# 06_-_CPU_-_ETHERNET_SATA.net
KiCad netlist of a schematic drawn in Altium Designer
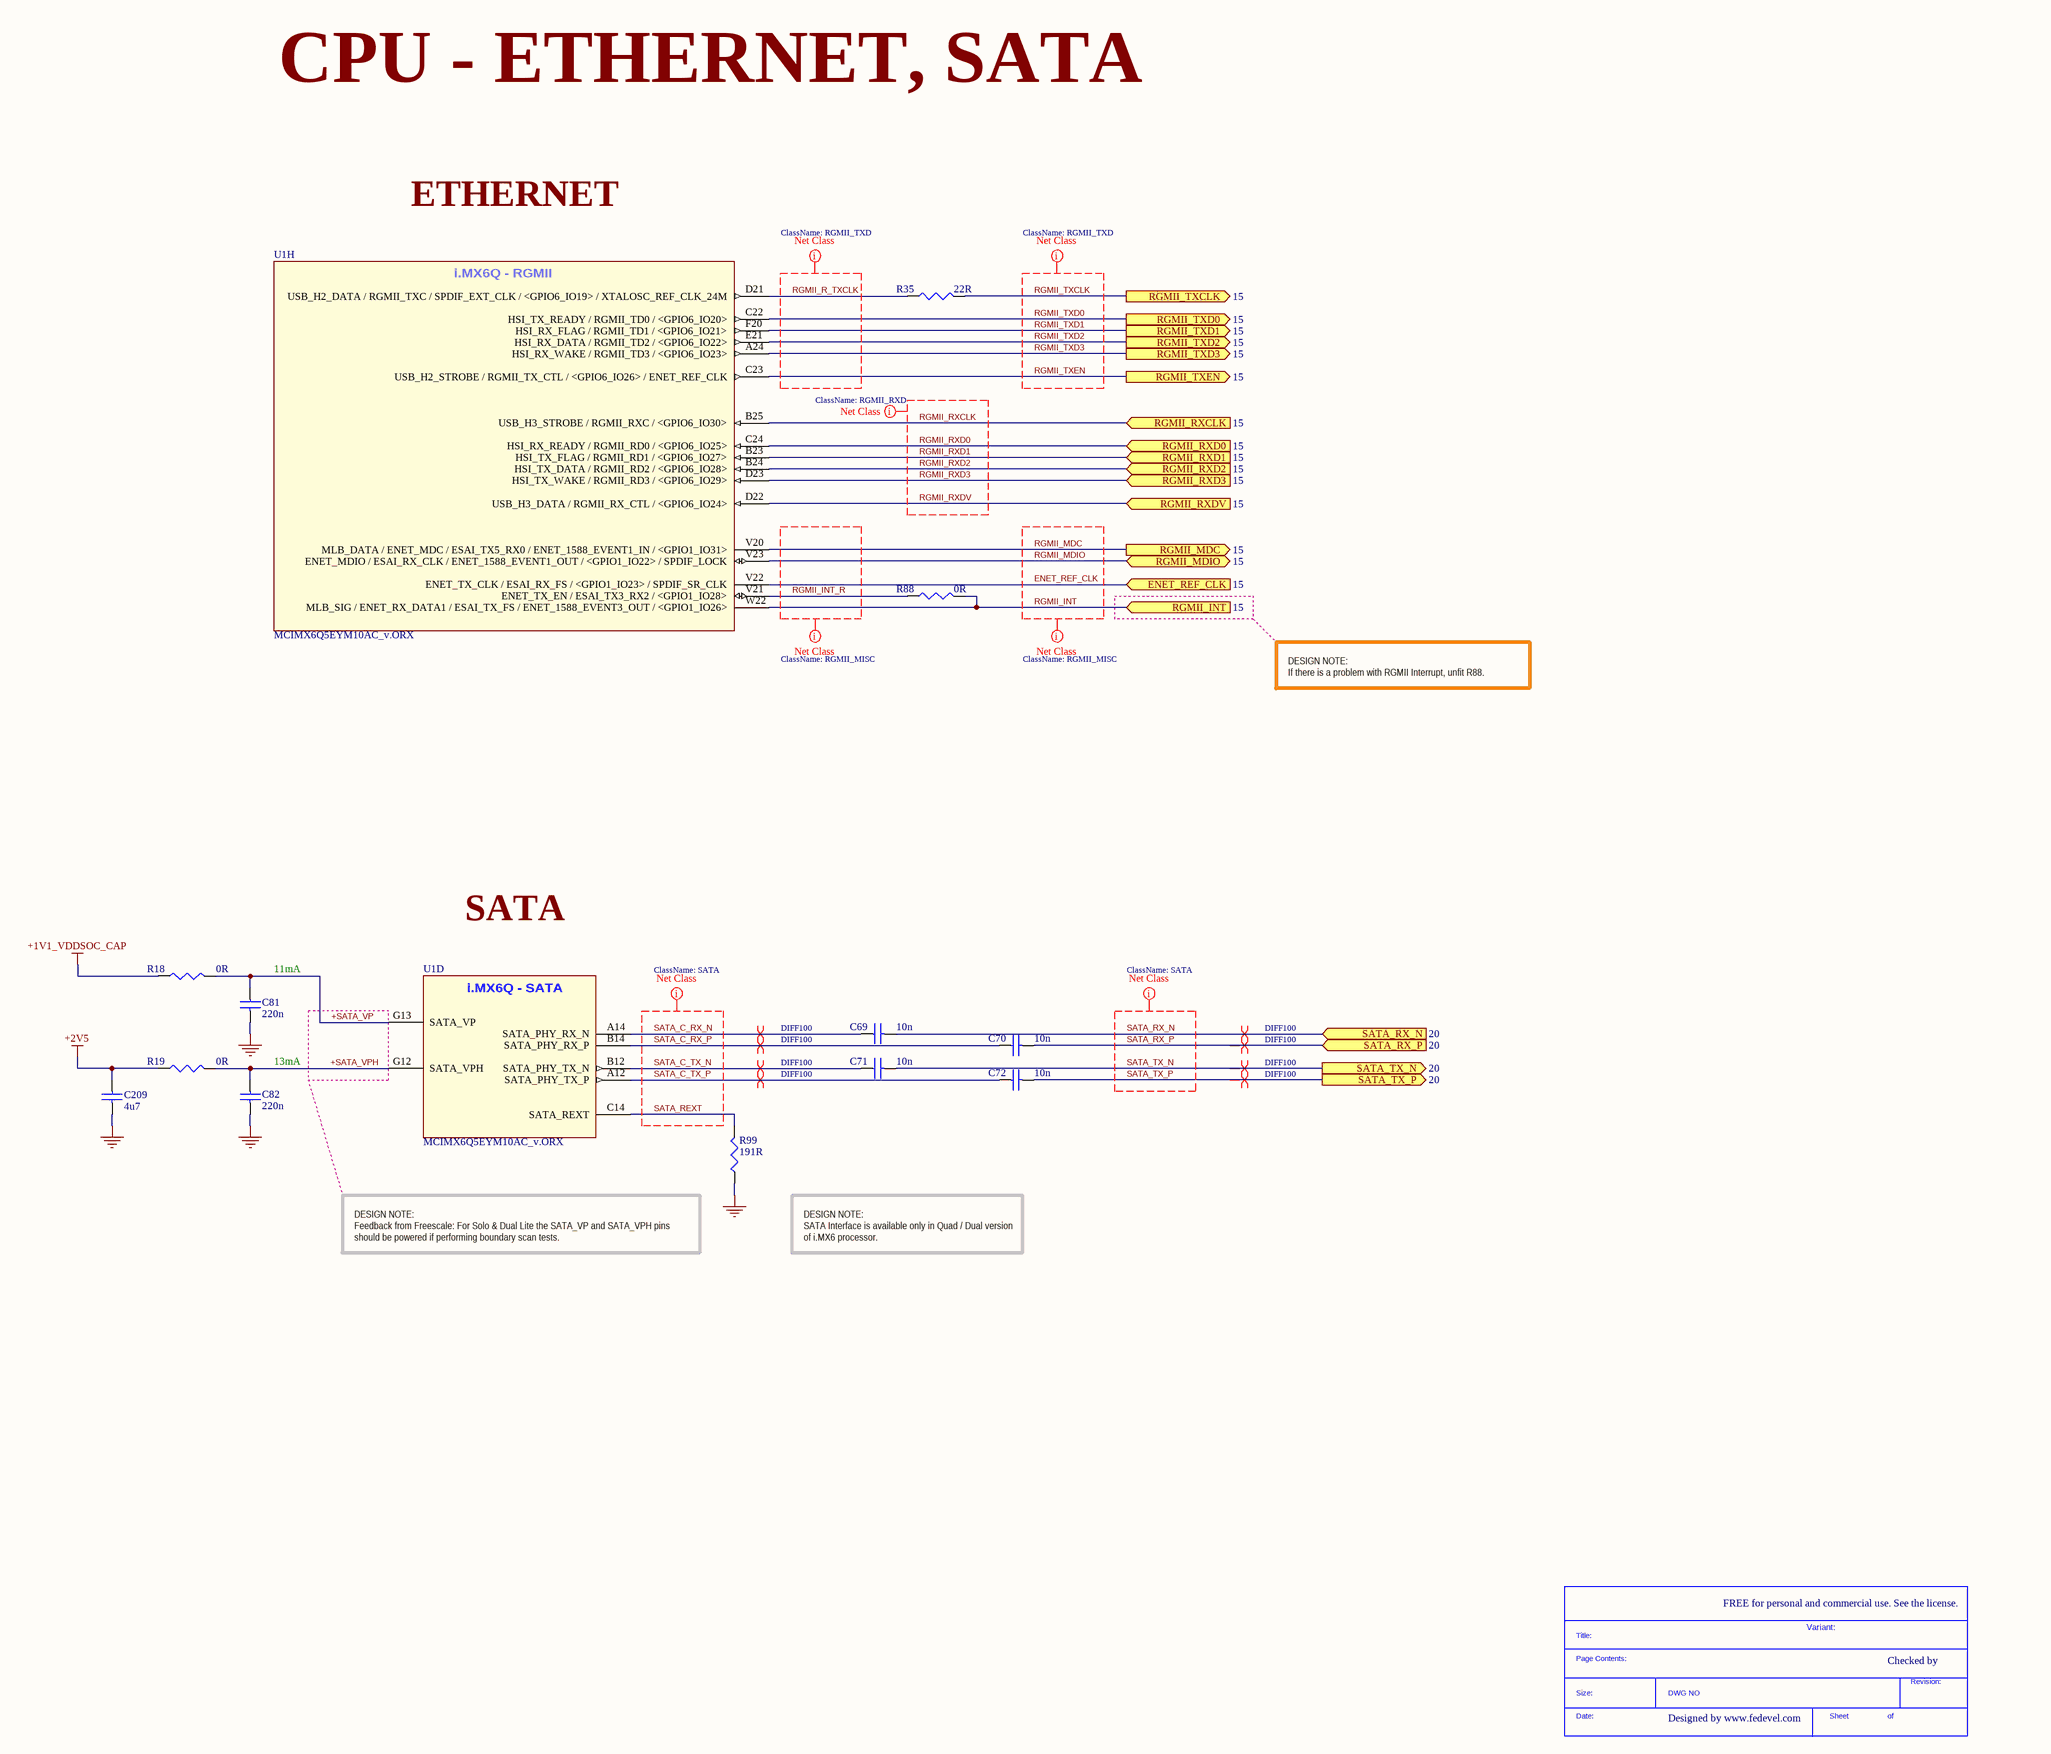
[diagram p0: [06] - CPU - ETHERNET, SATA.SchDoc]

(export (version "E")
  (design (tool "Eeschema 10.0.6"))
  (components
    (comp (ref "C69")
      (value "10n")
      (footprint "C0402")
      (description "CAP CER 10000PF 50V 10% X7R 0402")
      (fields
        (field (name "MANUFACTURER") "TDK Corporation")
        (field (name "MANUFACTURER PART NUMBER") "C1005X7R1H103K")
      )
      (libsource (lib "Integrated_Library_FEDEVEL_APR_2015") (part "C1005X7R1H103K"))
    )
    (comp (ref "C70")
      (value "10n")
      (footprint "C0402")
      (description "CAP CER 10000PF 50V 10% X7R 0402")
      (fields
        (field (name "MANUFACTURER") "TDK Corporation")
        (field (name "MANUFACTURER PART NUMBER") "C1005X7R1H103K")
      )
      (libsource (lib "Integrated_Library_FEDEVEL_APR_2015") (part "C1005X7R1H103K"))
    )
    (comp (ref "C71")
      (value "10n")
      (footprint "C0402")
      (description "CAP CER 10000PF 50V 10% X7R 0402")
      (fields
        (field (name "MANUFACTURER") "TDK Corporation")
        (field (name "MANUFACTURER PART NUMBER") "C1005X7R1H103K")
      )
      (libsource (lib "Integrated_Library_FEDEVEL_APR_2015") (part "C1005X7R1H103K"))
    )
    (comp (ref "C72")
      (value "10n")
      (footprint "C0402")
      (description "CAP CER 10000PF 50V 10% X7R 0402")
      (fields
        (field (name "MANUFACTURER") "TDK Corporation")
        (field (name "MANUFACTURER PART NUMBER") "C1005X7R1H103K")
      )
      (libsource (lib "Integrated_Library_FEDEVEL_APR_2015") (part "C1005X7R1H103K"))
    )
    (comp (ref "C81")
      (value "220n")
      (footprint "C0201")
      (description "CAP CER 0.22UF 6.3V 20% X5R 0201")
      (fields
        (field (name "MANUFACTURER") "TDK Corporation")
        (field (name "MANUFACTURER PART NUMBER") "C0603X5R0J224M030BB")
        (field (name ".CHECKED PCB") "MM")
        (field (name ".CHECKED SCH") "MM")
        (field (name ".CREATOR") "MM")
      )
      (libsource (lib "Integrated_Library_FEDEVEL_0201") (part "C0603X5R0J224M030BB"))
    )
    (comp (ref "C82")
      (value "220n")
      (footprint "C0201")
      (description "CAP CER 0.22UF 6.3V 20% X5R 0201")
      (fields
        (field (name "MANUFACTURER") "TDK Corporation")
        (field (name "MANUFACTURER PART NUMBER") "C0603X5R0J224M030BB")
        (field (name ".CHECKED PCB") "MM")
        (field (name ".CHECKED SCH") "MM")
        (field (name ".CREATOR") "MM")
      )
      (libsource (lib "Integrated_Library_FEDEVEL_0201") (part "C0603X5R0J224M030BB"))
    )
    (comp (ref "C209")
      (value "4u7")
      (footprint "C0402")
      (description "CAP CER 4.7UF 10V 20% X5R 0402")
      (fields
        (field (name "MANUFACTURER") "TDK Corporation")
        (field (name "MANUFACTURER PART NUMBER") "C1005X5R1A475M")
      )
      (libsource (lib "Integrated_Library_FEDEVEL_APR_2015") (part "C1005X5R1A475M"))
    )
    (comp (ref "R18")
      (value "0R")
      (footprint "R0402")
      (description "RES 0.0 OHM 1/16W 0402 SMD")
      (fields
        (field (name "MANUFACTURER") "Yageo")
        (field (name "MANUFACTURER PART NUMBER") "RC0402JR-070RL")
      )
      (libsource (lib "Integrated_Library_FEDEVEL_APR_2015") (part "RC0402JR-070RL"))
    )
    (comp (ref "R19")
      (value "0R")
      (footprint "R0402")
      (description "RES 0.0 OHM 1/16W 0402 SMD")
      (fields
        (field (name "MANUFACTURER") "Yageo")
        (field (name "MANUFACTURER PART NUMBER") "RC0402JR-070RL")
      )
      (libsource (lib "Integrated_Library_FEDEVEL_APR_2015") (part "RC0402JR-070RL"))
    )
    (comp (ref "R35")
      (value "22R")
      (footprint "R0402")
      (description "RES 22.0 OHM 1/16W 1% 0402 SMD")
      (fields
        (field (name "MANUFACTURER") "Yageo")
        (field (name "MANUFACTURER PART NUMBER") "RC0402FR-0722RL")
      )
      (libsource (lib "Integrated_Library_FEDEVEL_APR_2015") (part "RC0402FR-0722RL"))
    )
    (comp (ref "R88")
      (value "0R")
      (footprint "R0402")
      (description "RES 0.0 OHM 1/16W 0402 SMD")
      (fields
        (field (name "MANUFACTURER") "Yageo")
        (field (name "MANUFACTURER PART NUMBER") "RC0402JR-070RL")
      )
      (libsource (lib "Integrated_Library_FEDEVEL_APR_2015") (part "RC0402JR-070RL"))
    )
    (comp (ref "R99")
      (value "191R")
      (footprint "R0201")
      (description "RES 191 OHM 1/20W 1% 0201 SMD")
      (fields
        (field (name "MANUFACTURER") "Panasonic Electronic Components")
        (field (name "MANUFACTURER PART NUMBER") "ERJ-1GEF1910C")
        (field (name ".CREATOR") "MM")
        (field (name ".CHECKED PCB") "MM")
        (field (name ".CHECKED SCH") "MM")
      )
      (libsource (lib "Integrated_Library_FEDEVEL_0201") (part "ERJ-1GEF1910C"))
    )
    (comp (ref "U1")
      (value "MCIMX6Q5EYM10AC_v.ORX")
      (footprint "PBGA624")
      (description "IC MCU 32BIT ARM QUAD 624FCBGA")
      (fields
        (field (name "MANUFACTURER") "Freescale Semiconductor")
        (field (name "MANUFACTURER PART NUMBER") "MCIMX6Q5EYM10AC")
        (field (name ".CREATOR") "MM")
        (field (name ".CHECKED PCB") "MM, checked by RF")
      )
      (libsource (lib "Integrated_Library_FEDEVEL_APR_2015") (part "MCIMX6Q5EYM10AC_v.ORX"))
    )
  )
  (nets
    (net (code "1") (name "+1V1_VDDSOC_CAP") (class "Default")
      (node (ref "R18") (pin "1") (pinfunction "1_1") (pintype "passive"))
    )
    (net (code "2") (name "+2V5") (class "Default")
      (node (ref "C209") (pin "1") (pinfunction "1_1") (pintype "passive"))
      (node (ref "R19") (pin "1") (pinfunction "1_1") (pintype "passive"))
    )
    (net (code "3") (name "/+SATA_VP") (class "Default")
      (node (ref "C81") (pin "1") (pinfunction "1_1") (pintype "passive"))
      (node (ref "R18") (pin "2") (pinfunction "2_2") (pintype "passive"))
      (node (ref "U1") (pin "G13") (pinfunction "SATA_VP_G13") (pintype "power_in"))
    )
    (net (code "4") (name "/+SATA_VPH") (class "Default")
      (node (ref "C82") (pin "1") (pinfunction "1_1") (pintype "passive"))
      (node (ref "R19") (pin "2") (pinfunction "2_2") (pintype "passive"))
      (node (ref "U1") (pin "G12") (pinfunction "SATA_VPH_G12") (pintype "power_in"))
    )
    (net (code "5") (name "/ENET_REF_CLK") (class "Default")
      (node (ref "U1") (pin "V22") (pinfunction "ENET_TX_CLK_/_ESAI_RX_FS_/_<GPIO1_IO23>_/_SPDIF_SR_CLK_V22") (pintype "passive"))
    )
    (net (code "6") (name "/RGMII_INT") (class "Default")
      (node (ref "R88") (pin "2") (pinfunction "2_2") (pintype "passive"))
      (node (ref "U1") (pin "W22") (pinfunction "MLB_SIG_/_ENET_RX_DATA1_/_ESAI_TX_FS_/_ENET_1588_EVENT3_OUT_/_<GPIO1_IO26>_W22") (pintype "passive"))
    )
    (net (code "7") (name "/RGMII_INT_R") (class "Default")
      (node (ref "R88") (pin "1") (pinfunction "1_1") (pintype "passive"))
      (node (ref "U1") (pin "V21") (pinfunction "ENET_TX_EN_/_ESAI_TX3_RX2_/_<GPIO1_IO28>_V21") (pintype "bidirectional"))
    )
    (net (code "8") (name "/RGMII_MDC") (class "Default")
      (node (ref "U1") (pin "V20") (pinfunction "MLB_DATA_/_ENET_MDC_/_ESAI_TX5_RX0_/_ENET_1588_EVENT1_IN_/_<GPIO1_IO31>_V20") (pintype "passive"))
    )
    (net (code "9") (name "/RGMII_MDIO") (class "Default")
      (node (ref "U1") (pin "V23") (pinfunction "ENET_MDIO_/_ESAI_RX_CLK_/_ENET_1588_EVENT1_OUT_/_<GPIO1_IO22>_/_SPDIF_LOCK_V23") (pintype "bidirectional"))
    )
    (net (code "10") (name "/RGMII_RXCLK") (class "Default")
      (node (ref "U1") (pin "B25") (pinfunction "USB_H3_STROBE_/_RGMII_RXC_/_<GPIO6_IO30>_B25") (pintype "input"))
    )
    (net (code "11") (name "/RGMII_RXD0") (class "Default")
      (node (ref "U1") (pin "C24") (pinfunction "HSI_RX_READY_/_RGMII_RD0_/_<GPIO6_IO25>_C24") (pintype "input"))
    )
    (net (code "12") (name "/RGMII_RXD1") (class "Default")
      (node (ref "U1") (pin "B23") (pinfunction "HSI_TX_FLAG_/_RGMII_RD1_/_<GPIO6_IO27>_B23") (pintype "input"))
    )
    (net (code "13") (name "/RGMII_RXD2") (class "Default")
      (node (ref "U1") (pin "B24") (pinfunction "HSI_TX_DATA_/_RGMII_RD2_/_<GPIO6_IO28>_B24") (pintype "input"))
    )
    (net (code "14") (name "/RGMII_RXD3") (class "Default")
      (node (ref "U1") (pin "D23") (pinfunction "HSI_TX_WAKE_/_RGMII_RD3_/_<GPIO6_IO29>_D23") (pintype "input"))
    )
    (net (code "15") (name "/RGMII_RXDV") (class "Default")
      (node (ref "U1") (pin "D22") (pinfunction "USB_H3_DATA_/_RGMII_RX_CTL_/_<GPIO6_IO24>_D22") (pintype "input"))
    )
    (net (code "16") (name "/RGMII_R_TXCLK") (class "Default")
      (node (ref "R35") (pin "1") (pinfunction "1_1") (pintype "passive"))
      (node (ref "U1") (pin "D21") (pinfunction "USB_H2_DATA_/_RGMII_TXC_/_SPDIF_EXT_CLK_/_<GPIO6_IO19>_/_XTALOSC_REF_CLK_24M_D21") (pintype "output"))
    )
    (net (code "17") (name "/RGMII_TXCLK") (class "Default")
      (node (ref "R35") (pin "2") (pinfunction "2_2") (pintype "passive"))
    )
    (net (code "18") (name "/RGMII_TXD0") (class "Default")
      (node (ref "U1") (pin "C22") (pinfunction "HSI_TX_READY_/_RGMII_TD0_/_<GPIO6_IO20>_C22") (pintype "output"))
    )
    (net (code "19") (name "/RGMII_TXD1") (class "Default")
      (node (ref "U1") (pin "F20") (pinfunction "HSI_RX_FLAG_/_RGMII_TD1_/_<GPIO6_IO21>_F20") (pintype "output"))
    )
    (net (code "20") (name "/RGMII_TXD2") (class "Default")
      (node (ref "U1") (pin "E21") (pinfunction "HSI_RX_DATA_/_RGMII_TD2_/_<GPIO6_IO22>_E21") (pintype "output"))
    )
    (net (code "21") (name "/RGMII_TXD3") (class "Default")
      (node (ref "U1") (pin "A24") (pinfunction "HSI_RX_WAKE_/_RGMII_TD3_/_<GPIO6_IO23>_A24") (pintype "output"))
    )
    (net (code "22") (name "/RGMII_TXEN") (class "Default")
      (node (ref "U1") (pin "C23") (pinfunction "USB_H2_STROBE_/_RGMII_TX_CTL_/_<GPIO6_IO26>_/_ENET_REF_CLK_C23") (pintype "output"))
    )
    (net (code "23") (name "/SATA_C_RX_N") (class "Default")
      (node (ref "C69") (pin "1") (pinfunction "1_1") (pintype "passive"))
      (node (ref "U1") (pin "A14") (pinfunction "SATA_PHY_RX_N_A14") (pintype "passive"))
    )
    (net (code "24") (name "/SATA_C_RX_P") (class "Default")
      (node (ref "C70") (pin "1") (pinfunction "1_1") (pintype "passive"))
      (node (ref "U1") (pin "B14") (pinfunction "SATA_PHY_RX_P_B14") (pintype "passive"))
    )
    (net (code "25") (name "/SATA_C_TX_N") (class "Default")
      (node (ref "C71") (pin "1") (pinfunction "1_1") (pintype "passive"))
      (node (ref "U1") (pin "B12") (pinfunction "SATA_PHY_TX_N_B12") (pintype "output"))
    )
    (net (code "26") (name "/SATA_C_TX_P") (class "Default")
      (node (ref "C72") (pin "1") (pinfunction "1_1") (pintype "passive"))
      (node (ref "U1") (pin "A12") (pinfunction "SATA_PHY_TX_P_A12") (pintype "output"))
    )
    (net (code "27") (name "/SATA_REXT") (class "Default")
      (node (ref "R99") (pin "2") (pinfunction "2_2") (pintype "passive"))
      (node (ref "U1") (pin "C14") (pinfunction "SATA_REXT_C14") (pintype "passive"))
    )
    (net (code "28") (name "/SATA_RX_N") (class "Default")
      (node (ref "C69") (pin "2") (pinfunction "2_2") (pintype "passive"))
    )
    (net (code "29") (name "/SATA_RX_P") (class "Default")
      (node (ref "C70") (pin "2") (pinfunction "2_2") (pintype "passive"))
    )
    (net (code "30") (name "/SATA_TX_N") (class "Default")
      (node (ref "C71") (pin "2") (pinfunction "2_2") (pintype "passive"))
    )
    (net (code "31") (name "/SATA_TX_P") (class "Default")
      (node (ref "C72") (pin "2") (pinfunction "2_2") (pintype "passive"))
    )
    (net (code "32") (name "GND") (class "Default")
      (node (ref "C209") (pin "2") (pinfunction "2_2") (pintype "passive"))
      (node (ref "C81") (pin "2") (pinfunction "2_2") (pintype "passive"))
      (node (ref "C82") (pin "2") (pinfunction "2_2") (pintype "passive"))
      (node (ref "R99") (pin "1") (pinfunction "1_1") (pintype "passive"))
    )
  )
)
